# mcu_node.net
KiCad netlist of a schematic drawn in Altium Designer
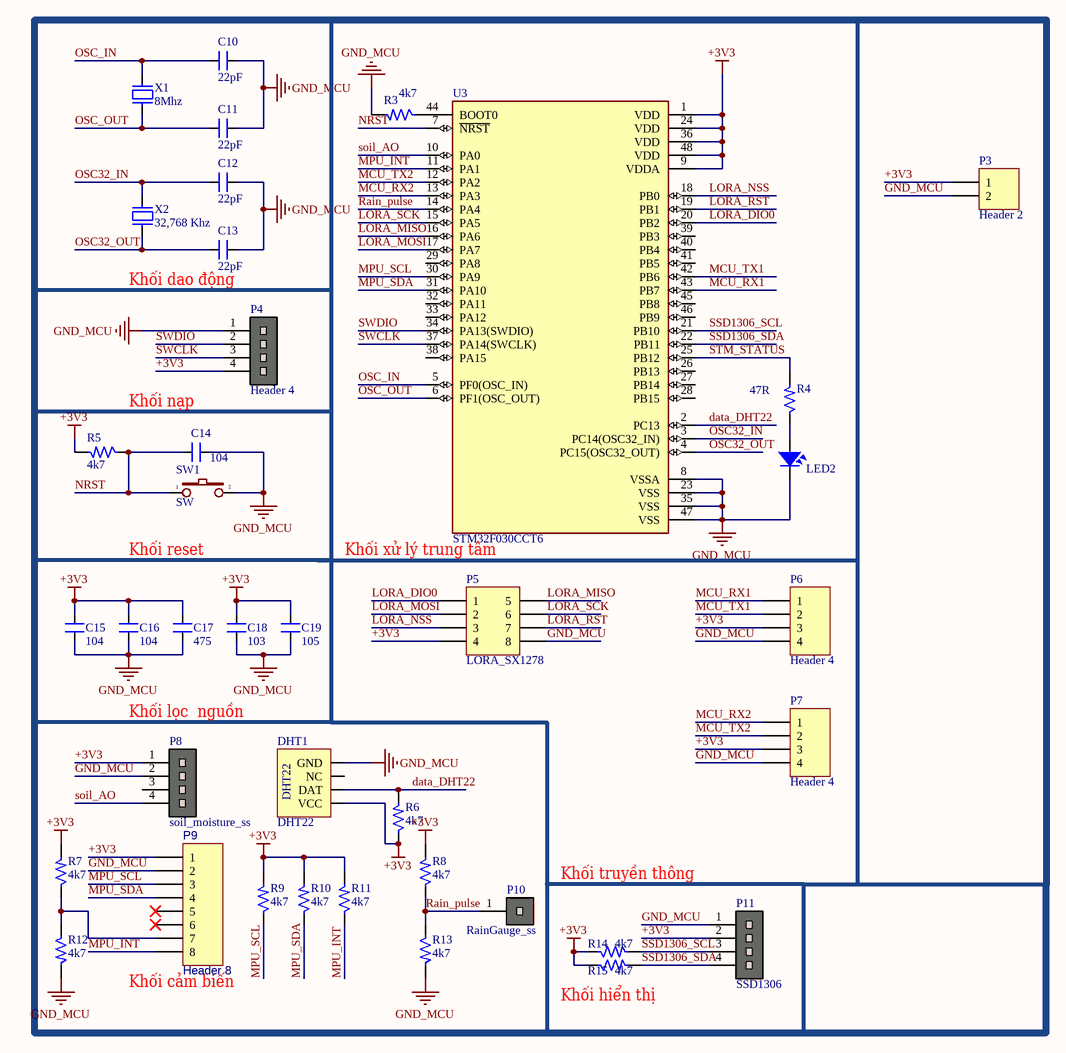
[diagram p0: mcu_node.SchDoc]

(export (version "E")
  (design (tool "Eeschema 10.0.6"))
  (components
    (comp (ref "C10")
      (value "22pF")
      (footprint "SM-0805")
      (description "Cap SMD")
      (libsource (lib "syhaunguyen") (part "CM"))
    )
    (comp (ref "C11")
      (value "22pF")
      (footprint "SM-0805")
      (description "Cap SMD")
      (libsource (lib "syhaunguyen") (part "CM"))
    )
    (comp (ref "C12")
      (value "22pF")
      (footprint "SM-0805")
      (description "Cap SMD")
      (libsource (lib "syhaunguyen") (part "CM"))
    )
    (comp (ref "C13")
      (value "22pF")
      (footprint "SM-0805")
      (description "Cap SMD")
      (libsource (lib "syhaunguyen") (part "CM"))
    )
    (comp (ref "C14")
      (value "104")
      (footprint "SM-0805")
      (description "Cap SMD")
      (libsource (lib "syhaunguyen") (part "CM"))
    )
    (comp (ref "C15")
      (value "104")
      (footprint "SM-0805")
      (description "Cap SMD")
      (libsource (lib "syhaunguyen") (part "CM"))
    )
    (comp (ref "C16")
      (value "104")
      (footprint "SM-0805")
      (description "Cap SMD")
      (libsource (lib "syhaunguyen") (part "CM"))
    )
    (comp (ref "C17")
      (value "475")
      (footprint "SM-0805")
      (description "Cap SMD")
      (libsource (lib "syhaunguyen") (part "CM"))
    )
    (comp (ref "C18")
      (value "103")
      (footprint "SM-0805")
      (description "Cap SMD")
      (libsource (lib "syhaunguyen") (part "CM"))
    )
    (comp (ref "C19")
      (value "105")
      (footprint "SM-0805")
      (description "Cap SMD")
      (libsource (lib "syhaunguyen") (part "CM"))
    )
    (comp (ref "DHT1")
      (value "DHT22")
      (footprint "DHT22")
      (fields
        (field (name "MANUFACTURER") "Würth Elektronik eiSos GmbH")
        (field (name "PARTNO") "613004143121")
        (field (name "CREATED BY") "Karrer Zheng")
      )
      (libsource (lib "TechMT.VN_Lib_Project v2") (part "DHT22"))
    )
    (comp (ref "LED2")
      (value "LED")
      (footprint "LED-0805-Green")
      (libsource (lib "TechMT.VN_Lib_Project v2") (part "LED SMD"))
    )
    (comp (ref "P3")
      (value "Header 2")
      (footprint "HDR1X2")
      (description "Header, 2-Pin")
      (fields (field (name "PUBLISHER") "Altium Limited"))
      (libsource (lib "Library AL") (part "Header 2"))
    )
    (comp (ref "P4")
      (value "Header 4")
      (footprint "HDR 1X4")
      (description "Header, 4-Pin")
      (libsource (lib "Ayric connectors") (part "Header 4"))
    )
    (comp (ref "P5")
      (value "LORA_SX1278")
      (footprint "HDR2X4_CEN")
      (description "Header, 4-Pin, Dual row")
      (fields (field (name "PUBLISHER") "Altium Limited"))
      (libsource (lib "Library AL") (part "Header 4X2A"))
    )
    (comp (ref "P6")
      (value "Header 4")
      (footprint "HDR1X4")
      (description "Header, 4-Pin")
      (fields (field (name "PUBLISHER") "Altium Limited"))
      (libsource (lib "Library AL") (part "Header 4"))
    )
    (comp (ref "P7")
      (value "Header 4")
      (footprint "HDR1X4")
      (description "Header, 4-Pin")
      (fields (field (name "PUBLISHER") "Altium Limited"))
      (libsource (lib "Library AL") (part "Header 4"))
    )
    (comp (ref "P8")
      (value "soil_moisture_ss")
      (footprint "HDR 1X4")
      (description "Header, 4-Pin")
      (libsource (lib "Ayric connectors") (part "Header 4"))
    )
    (comp (ref "P9")
      (value "Header 8")
      (footprint "HDR1X8")
      (description "Header, 8-Pin")
      (fields (field (name "PUBLISHER") "Altium Limited"))
      (libsource (lib "Library AL") (part "Header 8"))
    )
    (comp (ref "P10")
      (value "RainGauge_ss")
      (footprint "HDR 1X1")
      (description "Header, 1-Pin")
      (libsource (lib "Ayric connectors") (part "Header 1"))
    )
    (comp (ref "P11")
      (value "SSD1306")
      (footprint "HDR 1X4")
      (description "Header, 4-Pin")
      (libsource (lib "Ayric connectors") (part "Header 4"))
    )
    (comp (ref "R3")
      (value "4k7")
      (footprint "R-0805")
      (description "dien tro")
      (libsource (lib "oggy") (part "resistor"))
    )
    (comp (ref "R4")
      (value "47R")
      (footprint "R-0805")
      (description "dien tro")
      (libsource (lib "oggy") (part "resistor"))
    )
    (comp (ref "R5")
      (value "4k7")
      (footprint "R-0805")
      (description "dien tro")
      (libsource (lib "oggy") (part "resistor"))
    )
    (comp (ref "R6")
      (value "4k7")
      (footprint "R-0805")
      (description "dien tro")
      (libsource (lib "oggy") (part "resistor"))
    )
    (comp (ref "R7")
      (value "4k7")
      (footprint "R-0805")
      (description "dien tro")
      (libsource (lib "oggy") (part "resistor"))
    )
    (comp (ref "R8")
      (value "4k7")
      (footprint "R-0805")
      (description "dien tro")
      (libsource (lib "oggy") (part "resistor"))
    )
    (comp (ref "R9")
      (value "4k7")
      (footprint "R-0805")
      (description "dien tro")
      (libsource (lib "oggy") (part "resistor"))
    )
    (comp (ref "R10")
      (value "4k7")
      (footprint "R-0805")
      (description "dien tro")
      (libsource (lib "oggy") (part "resistor"))
    )
    (comp (ref "R11")
      (value "4k7")
      (footprint "R-0805")
      (description "dien tro")
      (libsource (lib "oggy") (part "resistor"))
    )
    (comp (ref "R12")
      (value "4k7")
      (footprint "R-0805")
      (description "dien tro")
      (libsource (lib "oggy") (part "resistor"))
    )
    (comp (ref "R13")
      (value "4k7")
      (footprint "R-0805")
      (description "dien tro")
      (libsource (lib "oggy") (part "resistor"))
    )
    (comp (ref "R14")
      (value "4k7")
      (footprint "R-0805")
      (description "dien tro")
      (libsource (lib "oggy") (part "resistor"))
    )
    (comp (ref "R15")
      (value "4k7")
      (footprint "R-0805")
      (description "dien tro")
      (libsource (lib "oggy") (part "resistor"))
    )
    (comp (ref "SW1")
      (value "SW")
      (footprint "SW1-SMD")
      (description "Switch button 2 pin")
      (libsource (lib "TechMT.VN_Lib_Project v2") (part "SW2"))
    )
    (comp (ref "U3")
      (value "STM32F030CCT6")
      (footprint "QFP50P900X900X160-48N")
      (description "ARMÂ® CortexÂ®-M0 STM32F0 Microcontroller IC 32-Bit 48MHz 256KB _256K x 8_ FLASH 48-LQFP _7x7_")
      (fields (field (name "MF") "STMicroelectronics") (field (name "DIGI-KEY_PART_NUMBER") "497-17332-2-ND"))
      (libsource (lib "STM32F030CCT6") (part "STM32F030CCT6"))
    )
    (comp (ref "X1")
      (value "8Mhz")
      (footprint "XT2")
      (description "Crystal For all Crystal 2pin.")
      (libsource (lib "syhaunguyen") (part "XT2"))
    )
    (comp (ref "X2")
      (value "32,768 Khz")
      (footprint "XT32k")
      (description "Crystal 32,768kHz for timer real")
      (libsource (lib "syhaunguyen") (part "XT32k"))
    )
  )
  (nets
    (net (code "1") (name "+3V3") (class "Default")
      (node (ref "C15") (pin "2") (pinfunction "2_2") (pintype "passive"))
      (node (ref "C16") (pin "2") (pinfunction "2_2") (pintype "passive"))
      (node (ref "C17") (pin "2") (pinfunction "2_2") (pintype "passive"))
      (node (ref "C18") (pin "2") (pinfunction "2_2") (pintype "passive"))
      (node (ref "C19") (pin "2") (pinfunction "2_2") (pintype "passive"))
      (node (ref "DHT1") (pin "1") (pinfunction "VCC_1") (pintype "passive"))
      (node (ref "P11") (pin "2") (pinfunction "2_2") (pintype "passive"))
      (node (ref "P3") (pin "1") (pinfunction "1_1") (pintype "passive"))
      (node (ref "P4") (pin "4") (pinfunction "4_4") (pintype "passive"))
      (node (ref "P5") (pin "4") (pinfunction "4_4") (pintype "passive"))
      (node (ref "P6") (pin "3") (pinfunction "3_3") (pintype "passive"))
      (node (ref "P7") (pin "3") (pinfunction "3_3") (pintype "passive"))
      (node (ref "P8") (pin "1") (pinfunction "1_1") (pintype "passive"))
      (node (ref "P9") (pin "1") (pinfunction "1_1") (pintype "passive"))
      (node (ref "R10") (pin "2") (pinfunction "2_2") (pintype "passive"))
      (node (ref "R11") (pin "2") (pinfunction "2_2") (pintype "passive"))
      (node (ref "R14") (pin "1") (pinfunction "1_1") (pintype "passive"))
      (node (ref "R15") (pin "1") (pinfunction "1_1") (pintype "passive"))
      (node (ref "R5") (pin "2") (pinfunction "2_2") (pintype "passive"))
      (node (ref "R6") (pin "1") (pinfunction "1_1") (pintype "passive"))
      (node (ref "R7") (pin "2") (pinfunction "2_2") (pintype "passive"))
      (node (ref "R8") (pin "2") (pinfunction "2_2") (pintype "passive"))
      (node (ref "R9") (pin "2") (pinfunction "2_2") (pintype "passive"))
      (node (ref "U3") (pin "1") (pinfunction "VDD_1") (pintype "power_in"))
      (node (ref "U3") (pin "24") (pinfunction "VDD_24") (pintype "power_in"))
      (node (ref "U3") (pin "36") (pinfunction "VDD_36") (pintype "power_in"))
      (node (ref "U3") (pin "48") (pinfunction "VDD_48") (pintype "power_in"))
      (node (ref "U3") (pin "9") (pinfunction "VDDA_9") (pintype "power_in"))
    )
    (net (code "2") (name "/LORA_DIO0") (class "Default")
      (node (ref "P5") (pin "1") (pinfunction "1_1") (pintype "passive"))
      (node (ref "U3") (pin "20") (pinfunction "PB2_20") (pintype "bidirectional"))
    )
    (net (code "3") (name "/LORA_MISO") (class "Default")
      (node (ref "P5") (pin "5") (pinfunction "5_5") (pintype "passive"))
      (node (ref "U3") (pin "16") (pinfunction "PA6_16") (pintype "bidirectional"))
    )
    (net (code "4") (name "/LORA_MOSI") (class "Default")
      (node (ref "P5") (pin "2") (pinfunction "2_2") (pintype "passive"))
      (node (ref "U3") (pin "17") (pinfunction "PA7_17") (pintype "bidirectional"))
    )
    (net (code "5") (name "/LORA_NSS") (class "Default")
      (node (ref "P5") (pin "3") (pinfunction "3_3") (pintype "passive"))
      (node (ref "U3") (pin "18") (pinfunction "PB0_18") (pintype "bidirectional"))
    )
    (net (code "6") (name "/LORA_RST") (class "Default")
      (node (ref "P5") (pin "7") (pinfunction "7_7") (pintype "passive"))
      (node (ref "U3") (pin "19") (pinfunction "PB1_19") (pintype "bidirectional"))
    )
    (net (code "7") (name "/LORA_SCK") (class "Default")
      (node (ref "P5") (pin "6") (pinfunction "6_6") (pintype "passive"))
      (node (ref "U3") (pin "15") (pinfunction "PA5_15") (pintype "bidirectional"))
    )
    (net (code "8") (name "/MCU_RX1") (class "Default")
      (node (ref "P6") (pin "1") (pinfunction "1_1") (pintype "passive"))
      (node (ref "U3") (pin "43") (pinfunction "PB7_43") (pintype "bidirectional"))
    )
    (net (code "9") (name "/MCU_RX2") (class "Default")
      (node (ref "P7") (pin "1") (pinfunction "1_1") (pintype "passive"))
      (node (ref "U3") (pin "13") (pinfunction "PA3_13") (pintype "bidirectional"))
    )
    (net (code "10") (name "/MCU_TX1") (class "Default")
      (node (ref "P6") (pin "2") (pinfunction "2_2") (pintype "passive"))
      (node (ref "U3") (pin "42") (pinfunction "PB6_42") (pintype "bidirectional"))
    )
    (net (code "11") (name "/MCU_TX2") (class "Default")
      (node (ref "P7") (pin "2") (pinfunction "2_2") (pintype "passive"))
      (node (ref "U3") (pin "12") (pinfunction "PA2_12") (pintype "bidirectional"))
    )
    (net (code "12") (name "/MPU_INT") (class "Default")
      (node (ref "P9") (pin "8") (pinfunction "8_8") (pintype "passive"))
      (node (ref "R11") (pin "1") (pinfunction "1_1") (pintype "passive"))
      (node (ref "U3") (pin "11") (pinfunction "PA1_11") (pintype "bidirectional"))
    )
    (net (code "13") (name "/MPU_SCL") (class "Default")
      (node (ref "P9") (pin "3") (pinfunction "3_3") (pintype "passive"))
      (node (ref "R9") (pin "1") (pinfunction "1_1") (pintype "passive"))
      (node (ref "U3") (pin "30") (pinfunction "PA9_30") (pintype "bidirectional"))
    )
    (net (code "14") (name "/MPU_SDA") (class "Default")
      (node (ref "P9") (pin "4") (pinfunction "4_4") (pintype "passive"))
      (node (ref "R10") (pin "1") (pinfunction "1_1") (pintype "passive"))
      (node (ref "U3") (pin "31") (pinfunction "PA10_31") (pintype "bidirectional"))
    )
    (net (code "15") (name "/NRST") (class "Default")
      (node (ref "C14") (pin "1") (pinfunction "1_1") (pintype "passive"))
      (node (ref "R5") (pin "1") (pinfunction "1_1") (pintype "passive"))
      (node (ref "SW1") (pin "1") (pinfunction "1_1") (pintype "passive"))
      (node (ref "U3") (pin "7") (pinfunction "~{NRST}_7") (pintype "bidirectional"))
    )
    (net (code "16") (name "/OSC32_IN") (class "Default")
      (node (ref "C12") (pin "2") (pinfunction "2_2") (pintype "passive"))
      (node (ref "U3") (pin "3") (pinfunction "PC14(OSC32_IN)_3") (pintype "bidirectional"))
      (node (ref "X2") (pin "2") (pinfunction "2_2") (pintype "passive"))
    )
    (net (code "17") (name "/OSC32_OUT") (class "Default")
      (node (ref "C13") (pin "2") (pinfunction "2_2") (pintype "passive"))
      (node (ref "U3") (pin "4") (pinfunction "PC15(OSC32_OUT)_4") (pintype "bidirectional"))
      (node (ref "X2") (pin "1") (pinfunction "1_1") (pintype "passive"))
    )
    (net (code "18") (name "/OSC_IN") (class "Default")
      (node (ref "C10") (pin "2") (pinfunction "2_2") (pintype "passive"))
      (node (ref "U3") (pin "5") (pinfunction "PF0(OSC_IN)_5") (pintype "bidirectional"))
      (node (ref "X1") (pin "2") (pinfunction "2_2") (pintype "passive"))
    )
    (net (code "19") (name "/OSC_OUT") (class "Default")
      (node (ref "C11") (pin "2") (pinfunction "2_2") (pintype "passive"))
      (node (ref "U3") (pin "6") (pinfunction "PF1(OSC_OUT)_6") (pintype "bidirectional"))
      (node (ref "X1") (pin "1") (pinfunction "1_1") (pintype "passive"))
    )
    (net (code "20") (name "/Rain_pulse") (class "Default")
      (node (ref "P10") (pin "1") (pinfunction "1_1") (pintype "passive"))
      (node (ref "R13") (pin "1") (pinfunction "1_1") (pintype "passive"))
      (node (ref "R8") (pin "1") (pinfunction "1_1") (pintype "passive"))
      (node (ref "U3") (pin "14") (pinfunction "PA4_14") (pintype "bidirectional"))
    )
    (net (code "21") (name "/SSD1306_SCL") (class "Default")
      (node (ref "P11") (pin "3") (pinfunction "3_3") (pintype "passive"))
      (node (ref "R14") (pin "2") (pinfunction "2_2") (pintype "passive"))
      (node (ref "U3") (pin "21") (pinfunction "PB10_21") (pintype "bidirectional"))
    )
    (net (code "22") (name "/SSD1306_SDA") (class "Default")
      (node (ref "P11") (pin "4") (pinfunction "4_4") (pintype "passive"))
      (node (ref "R15") (pin "2") (pinfunction "2_2") (pintype "passive"))
      (node (ref "U3") (pin "22") (pinfunction "PB11_22") (pintype "bidirectional"))
    )
    (net (code "23") (name "/STM_STATUS") (class "Default")
      (node (ref "R4") (pin "2") (pinfunction "2_2") (pintype "passive"))
      (node (ref "U3") (pin "25") (pinfunction "PB12_25") (pintype "bidirectional"))
    )
    (net (code "24") (name "/SWCLK") (class "Default")
      (node (ref "P4") (pin "3") (pinfunction "3_3") (pintype "passive"))
      (node (ref "U3") (pin "37") (pinfunction "PA14(SWCLK)_37") (pintype "bidirectional"))
    )
    (net (code "25") (name "/SWDIO") (class "Default")
      (node (ref "P4") (pin "2") (pinfunction "2_2") (pintype "passive"))
      (node (ref "U3") (pin "34") (pinfunction "PA13(SWDIO)_34") (pintype "bidirectional"))
    )
    (net (code "26") (name "/data_DHT22") (class "Default")
      (node (ref "DHT1") (pin "2") (pinfunction "DAT_2") (pintype "passive"))
      (node (ref "R6") (pin "2") (pinfunction "2_2") (pintype "passive"))
      (node (ref "U3") (pin "2") (pinfunction "PC13_2") (pintype "bidirectional"))
    )
    (net (code "27") (name "/soil_AO") (class "Default")
      (node (ref "P8") (pin "4") (pinfunction "4_4") (pintype "passive"))
      (node (ref "U3") (pin "10") (pinfunction "PA0_10") (pintype "bidirectional"))
    )
    (net (code "28") (name "GND_MCU") (class "Default")
      (node (ref "C10") (pin "1") (pinfunction "1_1") (pintype "passive"))
      (node (ref "C11") (pin "1") (pinfunction "1_1") (pintype "passive"))
      (node (ref "C12") (pin "1") (pinfunction "1_1") (pintype "passive"))
      (node (ref "C13") (pin "1") (pinfunction "1_1") (pintype "passive"))
      (node (ref "C14") (pin "2") (pinfunction "2_2") (pintype "passive"))
      (node (ref "C15") (pin "1") (pinfunction "1_1") (pintype "passive"))
      (node (ref "C16") (pin "1") (pinfunction "1_1") (pintype "passive"))
      (node (ref "C17") (pin "1") (pinfunction "1_1") (pintype "passive"))
      (node (ref "C18") (pin "1") (pinfunction "1_1") (pintype "passive"))
      (node (ref "C19") (pin "1") (pinfunction "1_1") (pintype "passive"))
      (node (ref "DHT1") (pin "4") (pinfunction "GND_4") (pintype "passive"))
      (node (ref "LED2") (pin "2") (pinfunction "2_2") (pintype "passive"))
      (node (ref "P11") (pin "1") (pinfunction "1_1") (pintype "passive"))
      (node (ref "P3") (pin "2") (pinfunction "2_2") (pintype "passive"))
      (node (ref "P4") (pin "1") (pinfunction "1_1") (pintype "passive"))
      (node (ref "P5") (pin "8") (pinfunction "8_8") (pintype "passive"))
      (node (ref "P6") (pin "4") (pinfunction "4_4") (pintype "passive"))
      (node (ref "P7") (pin "4") (pinfunction "4_4") (pintype "passive"))
      (node (ref "P8") (pin "2") (pinfunction "2_2") (pintype "passive"))
      (node (ref "P9") (pin "2") (pinfunction "2_2") (pintype "passive"))
      (node (ref "R12") (pin "2") (pinfunction "2_2") (pintype "passive"))
      (node (ref "R13") (pin "2") (pinfunction "2_2") (pintype "passive"))
      (node (ref "R3") (pin "2") (pinfunction "2_2") (pintype "passive"))
      (node (ref "SW1") (pin "2") (pinfunction "2_2") (pintype "passive"))
      (node (ref "U3") (pin "23") (pinfunction "VSS_23") (pintype "power_in"))
      (node (ref "U3") (pin "35") (pinfunction "VSS_35") (pintype "power_in"))
      (node (ref "U3") (pin "47") (pinfunction "VSS_47") (pintype "power_in"))
      (node (ref "U3") (pin "8") (pinfunction "VSSA_8") (pintype "power_in"))
    )
    (net (code "29") (name "Net-(LED2-Pad1)") (class "Default")
      (node (ref "LED2") (pin "1") (pinfunction "1_1") (pintype "passive"))
      (node (ref "R4") (pin "1") (pinfunction "1_1") (pintype "passive"))
    )
    (net (code "30") (name "Net-(P9-Pad7)") (class "Default")
      (node (ref "P9") (pin "7") (pinfunction "7_7") (pintype "passive"))
      (node (ref "R12") (pin "1") (pinfunction "1_1") (pintype "passive"))
      (node (ref "R7") (pin "1") (pinfunction "1_1") (pintype "passive"))
    )
    (net (code "31") (name "Net-(U3-BOOT0)") (class "Default")
      (node (ref "R3") (pin "1") (pinfunction "1_1") (pintype "passive"))
      (node (ref "U3") (pin "44") (pinfunction "BOOT0_44") (pintype "passive"))
    )
    (net (code "32") (name "unconnected-(DHT1-NC-Pad3)") (class "Default")
      (node (ref "DHT1") (pin "3") (pinfunction "NC_3") (pintype "passive"))
    )
    (net (code "33") (name "unconnected-(P8-Pad3)") (class "Default")
      (node (ref "P8") (pin "3") (pinfunction "3_3") (pintype "passive"))
    )
    (net (code "34") (name "unconnected-(P9-Pad5)") (class "Default")
      (node (ref "P9") (pin "5") (pinfunction "5_5") (pintype "passive+no_connect"))
    )
    (net (code "35") (name "unconnected-(P9-Pad6)") (class "Default")
      (node (ref "P9") (pin "6") (pinfunction "6_6") (pintype "passive+no_connect"))
    )
    (net (code "36") (name "unconnected-(U3-PA8-Pad29)") (class "Default")
      (node (ref "U3") (pin "29") (pinfunction "PA8_29") (pintype "bidirectional"))
    )
    (net (code "37") (name "unconnected-(U3-PA11-Pad32)") (class "Default")
      (node (ref "U3") (pin "32") (pinfunction "PA11_32") (pintype "bidirectional"))
    )
    (net (code "38") (name "unconnected-(U3-PA12-Pad33)") (class "Default")
      (node (ref "U3") (pin "33") (pinfunction "PA12_33") (pintype "bidirectional"))
    )
    (net (code "39") (name "unconnected-(U3-PA15-Pad38)") (class "Default")
      (node (ref "U3") (pin "38") (pinfunction "PA15_38") (pintype "bidirectional"))
    )
    (net (code "40") (name "unconnected-(U3-PB3-Pad39)") (class "Default")
      (node (ref "U3") (pin "39") (pinfunction "PB3_39") (pintype "bidirectional"))
    )
    (net (code "41") (name "unconnected-(U3-PB4-Pad40)") (class "Default")
      (node (ref "U3") (pin "40") (pinfunction "PB4_40") (pintype "bidirectional"))
    )
    (net (code "42") (name "unconnected-(U3-PB5-Pad41)") (class "Default")
      (node (ref "U3") (pin "41") (pinfunction "PB5_41") (pintype "bidirectional"))
    )
    (net (code "43") (name "unconnected-(U3-PB8-Pad45)") (class "Default")
      (node (ref "U3") (pin "45") (pinfunction "PB8_45") (pintype "bidirectional"))
    )
    (net (code "44") (name "unconnected-(U3-PB9-Pad46)") (class "Default")
      (node (ref "U3") (pin "46") (pinfunction "PB9_46") (pintype "bidirectional"))
    )
    (net (code "45") (name "unconnected-(U3-PB13-Pad26)") (class "Default")
      (node (ref "U3") (pin "26") (pinfunction "PB13_26") (pintype "bidirectional"))
    )
    (net (code "46") (name "unconnected-(U3-PB14-Pad27)") (class "Default")
      (node (ref "U3") (pin "27") (pinfunction "PB14_27") (pintype "bidirectional"))
    )
    (net (code "47") (name "unconnected-(U3-PB15-Pad28)") (class "Default")
      (node (ref "U3") (pin "28") (pinfunction "PB15_28") (pintype "bidirectional"))
    )
  )
)
